# LEDSEQUENCE.net
KiCad netlist of a schematic drawn in Altium Designer
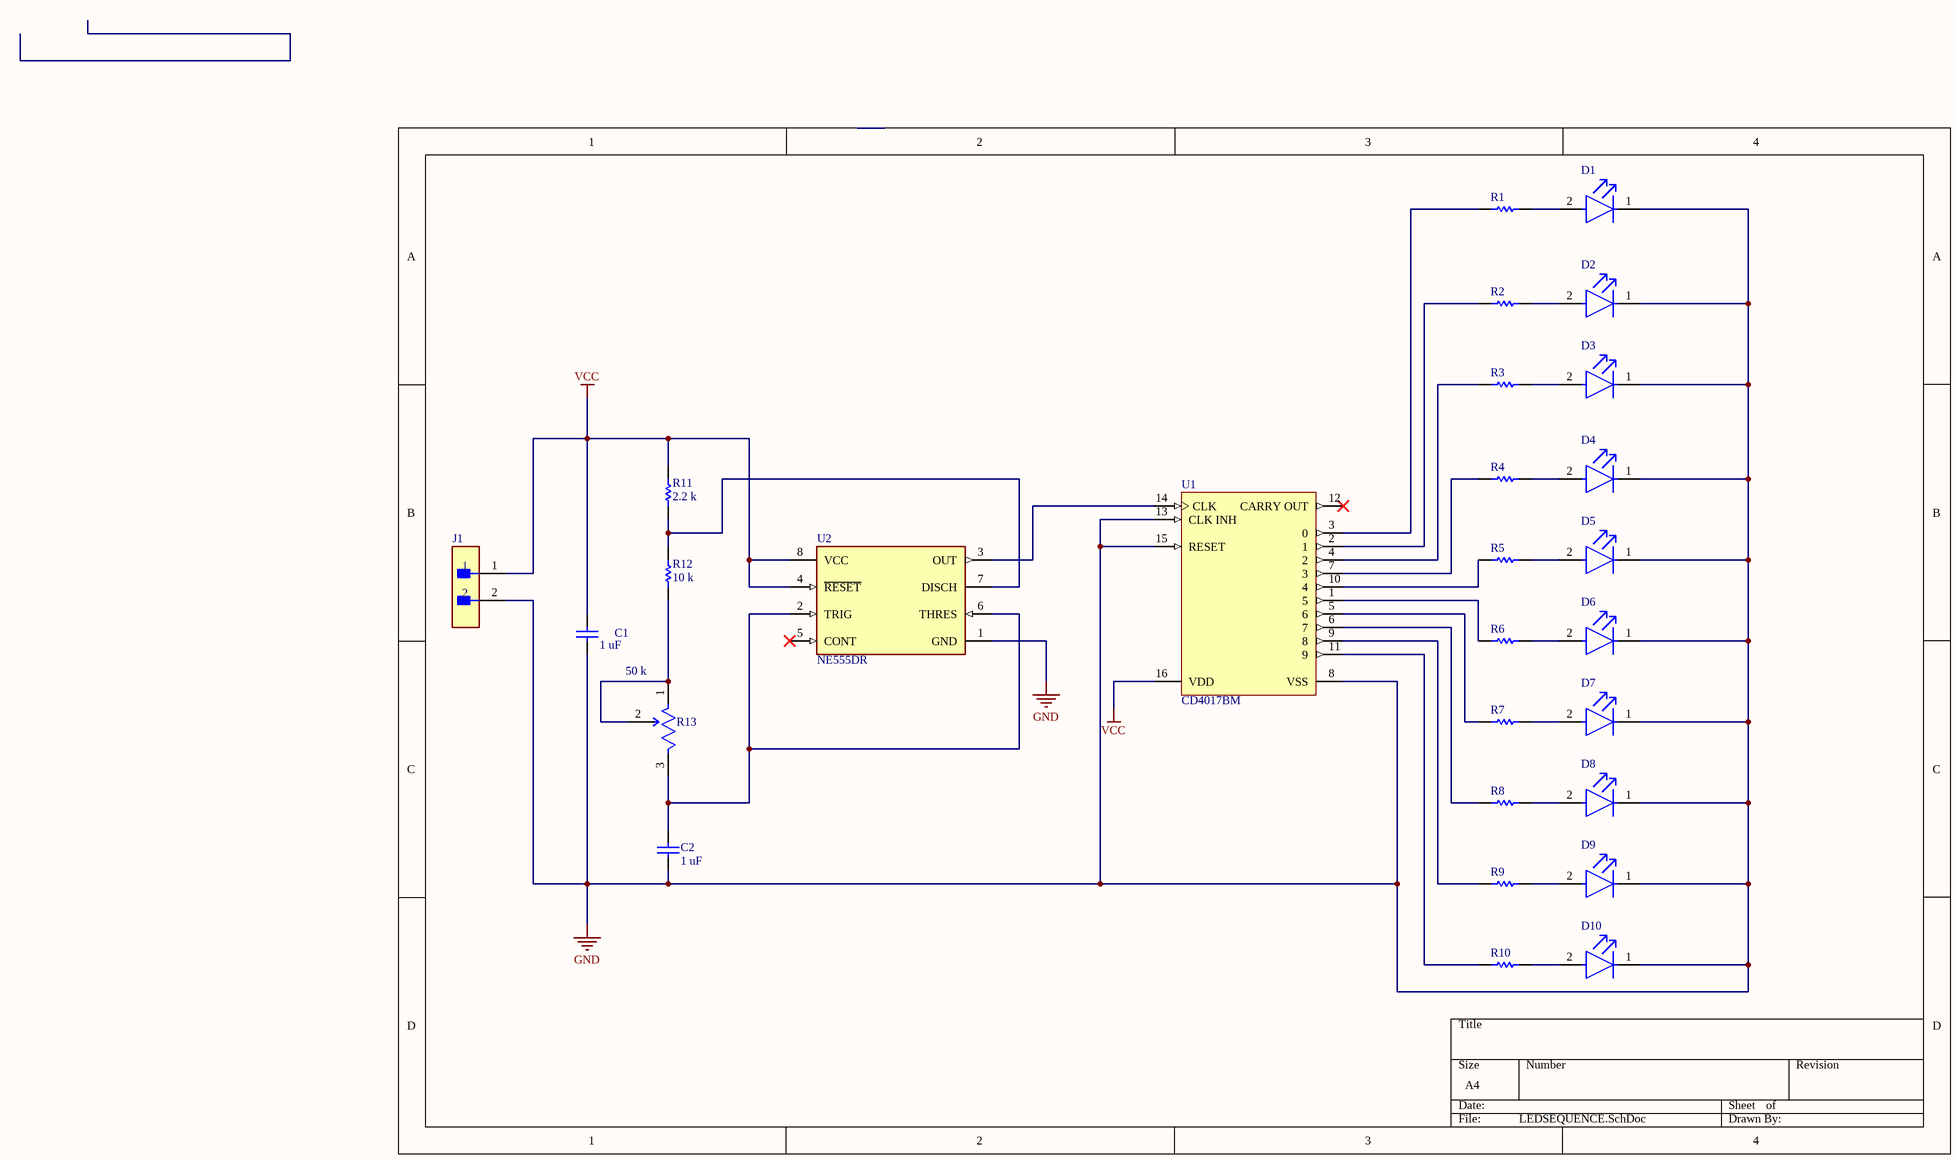
[diagram p0: LEDSEQUENCE.SchDoc]

(export (version "E")
  (design (tool "Eeschema 10.0.6"))
  (components
    (comp (ref "C1")
      (value "1 uF")
      (footprint "CAPC2013X135X45LL10T25")
      (fields (field (name "MANUFACTURER") "Murata") (field (name "PART NUMBER") "GRM21BR71H105KA12L"))
      (libsource (lib "Altium Content Vault") (part "CAP"))
    )
    (comp (ref "C2")
      (value "1 uF")
      (footprint "CAPC2013X135X45LL10T25")
      (fields (field (name "MANUFACTURER") "Murata") (field (name "PART NUMBER") "GRM21BR71H105KA12L"))
      (libsource (lib "Altium Content Vault") (part "CAP"))
    )
    (comp (ref "D1")
      (value "HLMP-1301")
      (footprint "FP-HLMP-1301-MFG")
      (description "LED RED DIFFUSED T-1 T/H")
      (fields
        (field (name "OCTOPART") "https://octopart.com/hlmp-1301-broadcom-71130345")
        (field (name "MANUFACTURER") "Broadcom")
      )
      (libsource (lib "Altium Content Vault") (part "8706943c75ba83719d021d2fdc84c58"))
    )
    (comp (ref "D2")
      (value "HLMP-1301")
      (footprint "FP-HLMP-1301-MFG")
      (description "LED RED DIFFUSED T-1 T/H")
      (fields
        (field (name "OCTOPART") "https://octopart.com/hlmp-1301-broadcom-71130345")
        (field (name "MANUFACTURER") "Broadcom")
      )
      (libsource (lib "Altium Content Vault") (part "8706943c75ba83719d021d2fdc84c58"))
    )
    (comp (ref "D3")
      (value "HLMP-1301")
      (footprint "FP-HLMP-1301-MFG")
      (description "LED RED DIFFUSED T-1 T/H")
      (fields
        (field (name "OCTOPART") "https://octopart.com/hlmp-1301-broadcom-71130345")
        (field (name "MANUFACTURER") "Broadcom")
      )
      (libsource (lib "Altium Content Vault") (part "8706943c75ba83719d021d2fdc84c58"))
    )
    (comp (ref "D4")
      (value "HLMP-1301")
      (footprint "FP-HLMP-1301-MFG")
      (description "LED RED DIFFUSED T-1 T/H")
      (fields
        (field (name "OCTOPART") "https://octopart.com/hlmp-1301-broadcom-71130345")
        (field (name "MANUFACTURER") "Broadcom")
      )
      (libsource (lib "Altium Content Vault") (part "8706943c75ba83719d021d2fdc84c58"))
    )
    (comp (ref "D5")
      (value "HLMP-1301")
      (footprint "FP-HLMP-1301-MFG")
      (description "LED RED DIFFUSED T-1 T/H")
      (fields
        (field (name "OCTOPART") "https://octopart.com/hlmp-1301-broadcom-71130345")
        (field (name "MANUFACTURER") "Broadcom")
      )
      (libsource (lib "Altium Content Vault") (part "8706943c75ba83719d021d2fdc84c58"))
    )
    (comp (ref "D6")
      (value "HLMP-1301")
      (footprint "FP-HLMP-1301-MFG")
      (description "LED RED DIFFUSED T-1 T/H")
      (fields
        (field (name "OCTOPART") "https://octopart.com/hlmp-1301-broadcom-71130345")
        (field (name "MANUFACTURER") "Broadcom")
      )
      (libsource (lib "Altium Content Vault") (part "8706943c75ba83719d021d2fdc84c58"))
    )
    (comp (ref "D7")
      (value "HLMP-1301")
      (footprint "FP-HLMP-1301-MFG")
      (description "LED RED DIFFUSED T-1 T/H")
      (fields
        (field (name "OCTOPART") "https://octopart.com/hlmp-1301-broadcom-71130345")
        (field (name "MANUFACTURER") "Broadcom")
      )
      (libsource (lib "Altium Content Vault") (part "8706943c75ba83719d021d2fdc84c58"))
    )
    (comp (ref "D8")
      (value "HLMP-1301")
      (footprint "FP-HLMP-1301-MFG")
      (description "LED RED DIFFUSED T-1 T/H")
      (fields
        (field (name "OCTOPART") "https://octopart.com/hlmp-1301-broadcom-71130345")
        (field (name "MANUFACTURER") "Broadcom")
      )
      (libsource (lib "Altium Content Vault") (part "8706943c75ba83719d021d2fdc84c58"))
    )
    (comp (ref "D9")
      (value "HLMP-1301")
      (footprint "FP-HLMP-1301-MFG")
      (description "LED RED DIFFUSED T-1 T/H")
      (fields
        (field (name "OCTOPART") "https://octopart.com/hlmp-1301-broadcom-71130345")
        (field (name "MANUFACTURER") "Broadcom")
      )
      (libsource (lib "Altium Content Vault") (part "8706943c75ba83719d021d2fdc84c58"))
    )
    (comp (ref "D10")
      (value "HLMP-1301")
      (footprint "FP-HLMP-1301-MFG")
      (description "LED RED DIFFUSED T-1 T/H")
      (fields
        (field (name "OCTOPART") "https://octopart.com/hlmp-1301-broadcom-71130345")
        (field (name "MANUFACTURER") "Broadcom")
      )
      (libsource (lib "Altium Content Vault") (part "8706943c75ba83719d021d2fdc84c58"))
    )
    (comp (ref "J1")
      (value "M20-9990246")
      (footprint "FP-M20-9990246-MFG")
      (description "CONN HEADER VERT 2POS 2.54MM")
      (fields
        (field (name "OCTOPART") "https://octopart.com/m20-9990246-harwin-2590635")
        (field (name "MANUFACTURER") "Harwin")
      )
      (libsource (lib "Altium Content Vault") (part "3bc925449376181038e59eaffc5286c"))
    )
    (comp (ref "R1")
      (value "RC0805FR-071KL")
      (footprint "RESC2013X60X35ML10T20")
      (description "Chip Resistor, 1 KOhm, +/- 1%, 125 mW, -55 to 155 degC, 0805 (2012 Metric), RoHS, Tape and Reel")
      (fields (field (name "TOLERANCE") "1%") (field (name "MANUFACTURER") "Yageo"))
      (libsource (lib "Altium Content Vault") (part "RES-2"))
    )
    (comp (ref "R2")
      (value "RC0805FR-071KL")
      (footprint "RESC2013X60X35ML10T20")
      (description "Chip Resistor, 1 KOhm, +/- 1%, 125 mW, -55 to 155 degC, 0805 (2012 Metric), RoHS, Tape and Reel")
      (fields (field (name "TOLERANCE") "1%") (field (name "MANUFACTURER") "Yageo"))
      (libsource (lib "Altium Content Vault") (part "RES-2"))
    )
    (comp (ref "R3")
      (value "RC0805FR-071KL")
      (footprint "RESC2013X60X35ML10T20")
      (description "Chip Resistor, 1 KOhm, +/- 1%, 125 mW, -55 to 155 degC, 0805 (2012 Metric), RoHS, Tape and Reel")
      (fields (field (name "TOLERANCE") "1%") (field (name "MANUFACTURER") "Yageo"))
      (libsource (lib "Altium Content Vault") (part "RES-2"))
    )
    (comp (ref "R4")
      (value "RC0805FR-071KL")
      (footprint "RESC2013X60X35ML10T20")
      (description "Chip Resistor, 1 KOhm, +/- 1%, 125 mW, -55 to 155 degC, 0805 (2012 Metric), RoHS, Tape and Reel")
      (fields (field (name "TOLERANCE") "1%") (field (name "MANUFACTURER") "Yageo"))
      (libsource (lib "Altium Content Vault") (part "RES-2"))
    )
    (comp (ref "R5")
      (value "RC0805FR-071KL")
      (footprint "RESC2013X60X35ML10T20")
      (description "Chip Resistor, 1 KOhm, +/- 1%, 125 mW, -55 to 155 degC, 0805 (2012 Metric), RoHS, Tape and Reel")
      (fields (field (name "TOLERANCE") "1%") (field (name "MANUFACTURER") "Yageo"))
      (libsource (lib "Altium Content Vault") (part "RES-2"))
    )
    (comp (ref "R6")
      (value "RC0805FR-071KL")
      (footprint "RESC2013X60X35ML10T20")
      (description "Chip Resistor, 1 KOhm, +/- 1%, 125 mW, -55 to 155 degC, 0805 (2012 Metric), RoHS, Tape and Reel")
      (fields (field (name "TOLERANCE") "1%") (field (name "MANUFACTURER") "Yageo"))
      (libsource (lib "Altium Content Vault") (part "RES-2"))
    )
    (comp (ref "R7")
      (value "RC0805FR-071KL")
      (footprint "RESC2013X60X35ML10T20")
      (description "Chip Resistor, 1 KOhm, +/- 1%, 125 mW, -55 to 155 degC, 0805 (2012 Metric), RoHS, Tape and Reel")
      (fields (field (name "TOLERANCE") "1%") (field (name "MANUFACTURER") "Yageo"))
      (libsource (lib "Altium Content Vault") (part "RES-2"))
    )
    (comp (ref "R8")
      (value "RC0805FR-071KL")
      (footprint "RESC2013X60X35ML10T20")
      (description "Chip Resistor, 1 KOhm, +/- 1%, 125 mW, -55 to 155 degC, 0805 (2012 Metric), RoHS, Tape and Reel")
      (fields (field (name "TOLERANCE") "1%") (field (name "MANUFACTURER") "Yageo"))
      (libsource (lib "Altium Content Vault") (part "RES-2"))
    )
    (comp (ref "R9")
      (value "RC0805FR-071KL")
      (footprint "RESC2013X60X35ML10T20")
      (description "Chip Resistor, 1 KOhm, +/- 1%, 125 mW, -55 to 155 degC, 0805 (2012 Metric), RoHS, Tape and Reel")
      (fields (field (name "TOLERANCE") "1%") (field (name "MANUFACTURER") "Yageo"))
      (libsource (lib "Altium Content Vault") (part "RES-2"))
    )
    (comp (ref "R10")
      (value "RC0805FR-071KL")
      (footprint "RESC2013X60X35ML10T20")
      (description "Chip Resistor, 1 KOhm, +/- 1%, 125 mW, -55 to 155 degC, 0805 (2012 Metric), RoHS, Tape and Reel")
      (fields (field (name "TOLERANCE") "1%") (field (name "MANUFACTURER") "Yageo"))
      (libsource (lib "Altium Content Vault") (part "RES-2"))
    )
    (comp (ref "R11")
      (value "2.2 k")
      (footprint "RESC2013X60X35ML10T20")
      (description "Chip Resistor, 1 KOhm, +/- 1%, 125 mW, -55 to 155 degC, 0805 (2012 Metric), RoHS, Tape and Reel")
      (fields (field (name "TOLERANCE") "1%") (field (name "MANUFACTURER") "Yageo"))
      (libsource (lib "Altium Content Vault") (part "RES-2"))
    )
    (comp (ref "R12")
      (value "10 k")
      (footprint "RESC2013X60X35ML10T20")
      (description "Chip Resistor, 1 KOhm, +/- 1%, 125 mW, -55 to 155 degC, 0805 (2012 Metric), RoHS, Tape and Reel")
      (fields (field (name "TOLERANCE") "1%") (field (name "MANUFACTURER") "Yageo"))
      (libsource (lib "Altium Content Vault") (part "RES-2"))
    )
    (comp (ref "R13")
      (value "50 k")
      (footprint "FP-3386P-MFG")
      (description "TRIMMER 100K OHM 0.5W PC PIN TOP")
      (fields (field (name "TOLERANCE") "10%"))
      (libsource (lib "Altium Content Vault") (part "13357d81287629c2fd191d242cfa50c"))
    )
    (comp (ref "U1")
      (value "CD4017BM")
      (footprint "D0016A_N")
      (description "CMOS Decade Counter with 10 Decoded Outputs, D0016A, TUBE")
      (fields
        (field (name "GENERIC PART NUMBER") "CD4017B")
        (field (name "MANUFACTURER") "Texas Instruments")
      )
      (libsource (lib "Altium Content Vault") (part "TI-CD4017B-16"))
    )
    (comp (ref "U2")
      (value "NE555DR")
      (footprint "FP-D0008A-IPC_A")
      (description "IC OSC SGL TIMER 100KHZ 8-SOIC")
      (libsource (lib "Altium Content Vault") (part "a29bba90211dec1890110b94dad7d53"))
    )
  )
  (nets
    (net (code "1") (name "GND") (class "Default")
      (node (ref "C1") (pin "1") (pinfunction "1_1") (pintype "passive"))
      (node (ref "C2") (pin "1") (pinfunction "1_1") (pintype "passive"))
      (node (ref "D1") (pin "1") (pinfunction "C_1") (pintype "passive"))
      (node (ref "D10") (pin "1") (pinfunction "C_1") (pintype "passive"))
      (node (ref "D2") (pin "1") (pinfunction "C_1") (pintype "passive"))
      (node (ref "D3") (pin "1") (pinfunction "C_1") (pintype "passive"))
      (node (ref "D4") (pin "1") (pinfunction "C_1") (pintype "passive"))
      (node (ref "D5") (pin "1") (pinfunction "C_1") (pintype "passive"))
      (node (ref "D6") (pin "1") (pinfunction "C_1") (pintype "passive"))
      (node (ref "D7") (pin "1") (pinfunction "C_1") (pintype "passive"))
      (node (ref "D8") (pin "1") (pinfunction "C_1") (pintype "passive"))
      (node (ref "D9") (pin "1") (pinfunction "C_1") (pintype "passive"))
      (node (ref "J1") (pin "2") (pinfunction "2_2") (pintype "passive"))
      (node (ref "U1") (pin "13") (pinfunction "CLK_INH_13") (pintype "input"))
      (node (ref "U1") (pin "15") (pinfunction "RESET_15") (pintype "input"))
      (node (ref "U1") (pin "8") (pinfunction "VSS_8") (pintype "power_in"))
      (node (ref "U2") (pin "1") (pinfunction "GND_1") (pintype "power_in"))
    )
    (net (code "2") (name "Net-(D1-A)") (class "Default")
      (node (ref "D1") (pin "2") (pinfunction "A_2") (pintype "passive"))
      (node (ref "R1") (pin "2") (pinfunction "2_2") (pintype "passive"))
    )
    (net (code "3") (name "Net-(D2-A)") (class "Default")
      (node (ref "D2") (pin "2") (pinfunction "A_2") (pintype "passive"))
      (node (ref "R2") (pin "2") (pinfunction "2_2") (pintype "passive"))
    )
    (net (code "4") (name "Net-(D3-A)") (class "Default")
      (node (ref "D3") (pin "2") (pinfunction "A_2") (pintype "passive"))
      (node (ref "R3") (pin "2") (pinfunction "2_2") (pintype "passive"))
    )
    (net (code "5") (name "Net-(D4-A)") (class "Default")
      (node (ref "D4") (pin "2") (pinfunction "A_2") (pintype "passive"))
      (node (ref "R4") (pin "2") (pinfunction "2_2") (pintype "passive"))
    )
    (net (code "6") (name "Net-(D5-A)") (class "Default")
      (node (ref "D5") (pin "2") (pinfunction "A_2") (pintype "passive"))
      (node (ref "R5") (pin "2") (pinfunction "2_2") (pintype "passive"))
    )
    (net (code "7") (name "Net-(D6-A)") (class "Default")
      (node (ref "D6") (pin "2") (pinfunction "A_2") (pintype "passive"))
      (node (ref "R6") (pin "2") (pinfunction "2_2") (pintype "passive"))
    )
    (net (code "8") (name "Net-(D7-A)") (class "Default")
      (node (ref "D7") (pin "2") (pinfunction "A_2") (pintype "passive"))
      (node (ref "R7") (pin "2") (pinfunction "2_2") (pintype "passive"))
    )
    (net (code "9") (name "Net-(D8-A)") (class "Default")
      (node (ref "D8") (pin "2") (pinfunction "A_2") (pintype "passive"))
      (node (ref "R8") (pin "2") (pinfunction "2_2") (pintype "passive"))
    )
    (net (code "10") (name "Net-(D9-A)") (class "Default")
      (node (ref "D9") (pin "2") (pinfunction "A_2") (pintype "passive"))
      (node (ref "R9") (pin "2") (pinfunction "2_2") (pintype "passive"))
    )
    (net (code "11") (name "Net-(D10-A)") (class "Default")
      (node (ref "D10") (pin "2") (pinfunction "A_2") (pintype "passive"))
      (node (ref "R10") (pin "2") (pinfunction "2_2") (pintype "passive"))
    )
    (net (code "12") (name "Net-(R13-CCW)") (class "Default")
      (node (ref "R12") (pin "1") (pinfunction "1_1") (pintype "passive"))
      (node (ref "R13") (pin "1") (pinfunction "CCW_1") (pintype "passive"))
      (node (ref "R13") (pin "2") (pinfunction "WIPER_2") (pintype "passive"))
    )
    (net (code "13") (name "Net-(R13-CW)") (class "Default")
      (node (ref "C2") (pin "2") (pinfunction "2_2") (pintype "passive"))
      (node (ref "R13") (pin "3") (pinfunction "CW_3") (pintype "passive"))
      (node (ref "U2") (pin "2") (pinfunction "TRIG_2") (pintype "input"))
      (node (ref "U2") (pin "6") (pinfunction "THRES_6") (pintype "input"))
    )
    (net (code "14") (name "Net-(U1-0)") (class "Default")
      (node (ref "R1") (pin "1") (pinfunction "1_1") (pintype "passive"))
      (node (ref "U1") (pin "3") (pinfunction "0_3") (pintype "output"))
    )
    (net (code "15") (name "Net-(U1-1)") (class "Default")
      (node (ref "R2") (pin "1") (pinfunction "1_1") (pintype "passive"))
      (node (ref "U1") (pin "2") (pinfunction "1_2") (pintype "output"))
    )
    (net (code "16") (name "Net-(U1-2)") (class "Default")
      (node (ref "R3") (pin "1") (pinfunction "1_1") (pintype "passive"))
      (node (ref "U1") (pin "4") (pinfunction "2_4") (pintype "output"))
    )
    (net (code "17") (name "Net-(U1-3)") (class "Default")
      (node (ref "R4") (pin "1") (pinfunction "1_1") (pintype "passive"))
      (node (ref "U1") (pin "7") (pinfunction "3_7") (pintype "output"))
    )
    (net (code "18") (name "Net-(U1-4)") (class "Default")
      (node (ref "R5") (pin "1") (pinfunction "1_1") (pintype "passive"))
      (node (ref "U1") (pin "10") (pinfunction "4_10") (pintype "output"))
    )
    (net (code "19") (name "Net-(U1-5)") (class "Default")
      (node (ref "R6") (pin "1") (pinfunction "1_1") (pintype "passive"))
      (node (ref "U1") (pin "1") (pinfunction "5_1") (pintype "output"))
    )
    (net (code "20") (name "Net-(U1-6)") (class "Default")
      (node (ref "R7") (pin "1") (pinfunction "1_1") (pintype "passive"))
      (node (ref "U1") (pin "5") (pinfunction "6_5") (pintype "output"))
    )
    (net (code "21") (name "Net-(U1-7)") (class "Default")
      (node (ref "R8") (pin "1") (pinfunction "1_1") (pintype "passive"))
      (node (ref "U1") (pin "6") (pinfunction "7_6") (pintype "output"))
    )
    (net (code "22") (name "Net-(U1-8)") (class "Default")
      (node (ref "R9") (pin "1") (pinfunction "1_1") (pintype "passive"))
      (node (ref "U1") (pin "9") (pinfunction "8_9") (pintype "output"))
    )
    (net (code "23") (name "Net-(U1-9)") (class "Default")
      (node (ref "R10") (pin "1") (pinfunction "1_1") (pintype "passive"))
      (node (ref "U1") (pin "11") (pinfunction "9_11") (pintype "output"))
    )
    (net (code "24") (name "Net-(U1-CLK)") (class "Default")
      (node (ref "U1") (pin "14") (pinfunction "CLK_14") (pintype "input"))
      (node (ref "U2") (pin "3") (pinfunction "OUT_3") (pintype "output"))
    )
    (net (code "25") (name "Net-(U2-DISCH)") (class "Default")
      (node (ref "R11") (pin "1") (pinfunction "1_1") (pintype "passive"))
      (node (ref "R12") (pin "2") (pinfunction "2_2") (pintype "passive"))
      (node (ref "U2") (pin "7") (pinfunction "DISCH_7") (pintype "open_collector"))
    )
    (net (code "26") (name "VCC") (class "Default")
      (node (ref "C1") (pin "2") (pinfunction "2_2") (pintype "passive"))
      (node (ref "J1") (pin "1") (pinfunction "1_1") (pintype "passive"))
      (node (ref "R11") (pin "2") (pinfunction "2_2") (pintype "passive"))
      (node (ref "U1") (pin "16") (pinfunction "VDD_16") (pintype "power_in"))
      (node (ref "U2") (pin "4") (pinfunction "~{RESET}_4") (pintype "input"))
      (node (ref "U2") (pin "8") (pinfunction "VCC_8") (pintype "power_in"))
    )
    (net (code "27") (name "unconnected-(U1-CARRY_OUT-Pad12)") (class "Default")
      (node (ref "U1") (pin "12") (pinfunction "CARRY_OUT_12") (pintype "output+no_connect"))
    )
    (net (code "28") (name "unconnected-(U2-CONT-Pad5)") (class "Default")
      (node (ref "U2") (pin "5") (pinfunction "CONT_5") (pintype "input+no_connect"))
    )
  )
)
